# ArduinoRelayTimerSche.net
KiCad netlist of a schematic drawn in Altium Designer
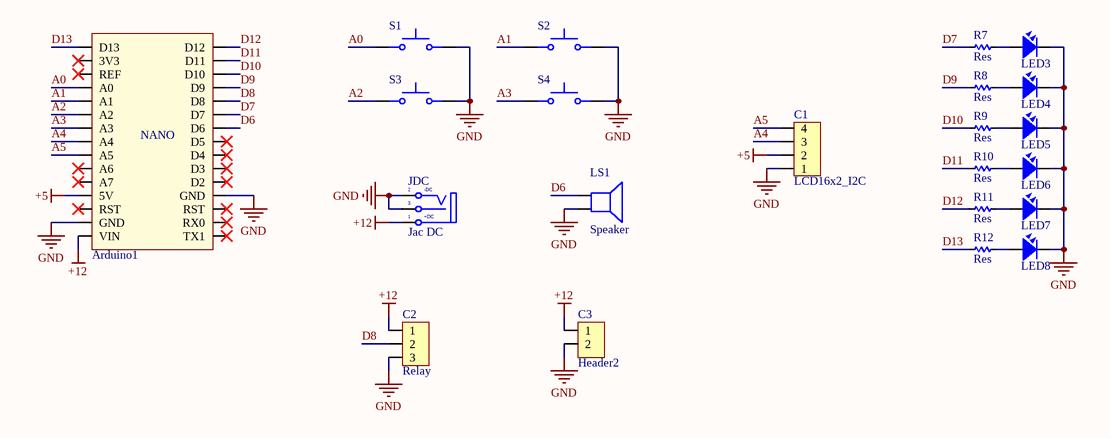
[diagram p0: ArduinoRelayTimerSche.SchDoc]

(export (version "E")
  (design (tool "Eeschema 10.0.6"))
  (components
    (comp (ref "Arduino1")
      (value "Arduino Nano")
      (footprint "Arduino Nano")
      (description "Arduino NANO")
      (libsource (lib "LIBRARY") (part "Arduino Nano"))
    )
    (comp (ref "C1")
      (value "LCD16x2_I2C")
      (footprint "Header4")
      (description "Header IDC, 4 x 1 Pin Vertical 2.54mm Pitch (Non-Boxed, Male)")
      (fields
        (field (name "MANUFACTURER") "Würth Elektronik eiSos GmbH")
        (field (name "PARTNO") "613002143121")
        (field (name "CREATED BY") "Karrer Zheng")
      )
      (libsource (lib "LIBRARY") (part "Header4"))
    )
    (comp (ref "C2")
      (value "Relay")
      (footprint "Header3")
      (description "Header IDC, 3 x 1 Pin Vertical 2.54mm Pitch (Non-Boxed, Male)")
      (fields
        (field (name "MANUFACTURER") "Würth Elektronik eiSos GmbH")
        (field (name "PARTNO") "613002143121")
        (field (name "CREATED BY") "Karrer Zheng")
      )
      (libsource (lib "LIBRARY") (part "Header3"))
    )
    (comp (ref "C3")
      (value "Header2")
      (footprint "Header2")
      (description "Header IDC, 2 x 1 Pin Vertical 2.54mm Pitch (Non-Boxed, Male)")
      (fields
        (field (name "MANUFACTURER") "Würth Elektronik eiSos GmbH")
        (field (name "PARTNO") "613002143121")
        (field (name "CREATED BY") "Karrer Zheng")
      )
      (libsource (lib "LIBRARY") (part "Header2"))
    )
    (comp (ref "JDC")
      (value "Jac DC")
      (footprint "DC0")
      (description "Jac DC input")
      (libsource (lib "LIBRARY") (part "DCIN"))
    )
    (comp (ref "LED3")
      (value "LED")
      (footprint "LED-5-Yellow")
      (description "LED Single colour Green and Red")
      (libsource (lib "LIBRARY") (part "LED"))
    )
    (comp (ref "LED4")
      (value "LED")
      (footprint "LED-5-Yellow")
      (description "LED Single colour Green and Red")
      (libsource (lib "LIBRARY") (part "LED"))
    )
    (comp (ref "LED5")
      (value "LED")
      (footprint "LED-5-Yellow")
      (description "LED Single colour Green and Red")
      (libsource (lib "LIBRARY") (part "LED"))
    )
    (comp (ref "LED6")
      (value "LED")
      (footprint "LED-5-Yellow")
      (description "LED Single colour Green and Red")
      (libsource (lib "LIBRARY") (part "LED"))
    )
    (comp (ref "LED7")
      (value "LED")
      (footprint "LED-5-Yellow")
      (description "LED Single colour Green and Red")
      (libsource (lib "LIBRARY") (part "LED"))
    )
    (comp (ref "LED8")
      (value "LED")
      (footprint "LED-5-Yellow")
      (description "LED Single colour Green and Red")
      (libsource (lib "LIBRARY") (part "LED"))
    )
    (comp (ref "LS1")
      (value "Speaker")
      (footprint "SPEAKER")
      (description "Loudspeaker")
      (fields (field (name "PUBLISHER") "Altium Limited"))
      (libsource (lib "LIBRARY") (part "Speaker"))
    )
    (comp (ref "R7")
      (value "Res")
      (footprint "RES-1/4W-SMALL")
      (fields
        (field (name "MANUFACTURER") "Generic Components")
        (field (name "PUBLISHER") "Altium Hobart Technology Centre")
      )
      (libsource (lib "LIBRARY") (part "Res"))
    )
    (comp (ref "R8")
      (value "Res")
      (footprint "RES-1/4W-SMALL")
      (fields
        (field (name "MANUFACTURER") "Generic Components")
        (field (name "PUBLISHER") "Altium Hobart Technology Centre")
      )
      (libsource (lib "LIBRARY") (part "Res"))
    )
    (comp (ref "R9")
      (value "Res")
      (footprint "RES-1/4W-SMALL")
      (fields
        (field (name "MANUFACTURER") "Generic Components")
        (field (name "PUBLISHER") "Altium Hobart Technology Centre")
      )
      (libsource (lib "LIBRARY") (part "Res"))
    )
    (comp (ref "R10")
      (value "Res")
      (footprint "RES-1/4W-SMALL")
      (fields
        (field (name "MANUFACTURER") "Generic Components")
        (field (name "PUBLISHER") "Altium Hobart Technology Centre")
      )
      (libsource (lib "LIBRARY") (part "Res"))
    )
    (comp (ref "R11")
      (value "Res")
      (footprint "RES-1/4W-SMALL")
      (fields
        (field (name "MANUFACTURER") "Generic Components")
        (field (name "PUBLISHER") "Altium Hobart Technology Centre")
      )
      (libsource (lib "LIBRARY") (part "Res"))
    )
    (comp (ref "R12")
      (value "Res")
      (footprint "RES-1/4W-SMALL")
      (fields
        (field (name "MANUFACTURER") "Generic Components")
        (field (name "PUBLISHER") "Altium Hobart Technology Centre")
      )
      (libsource (lib "LIBRARY") (part "Res"))
    )
    (comp (ref "S1")
      (value "~")
      (footprint "SW_TL59NF160Q")
      (description "SWITCH TACTILE SPST-NO 0.05A 12V")
      (fields (field (name "MF") "E-Switch") (field (name "MP") "TL59NF160Q"))
      (libsource (lib "BigTactileSwitch2pins") (part "TL59NF160Q"))
    )
    (comp (ref "S2")
      (value "~")
      (footprint "SW_TL59NF160Q")
      (description "SWITCH TACTILE SPST-NO 0.05A 12V")
      (fields (field (name "MF") "E-Switch") (field (name "MP") "TL59NF160Q"))
      (libsource (lib "BigTactileSwitch2pins") (part "TL59NF160Q"))
    )
    (comp (ref "S3")
      (value "~")
      (footprint "SW_TL59NF160Q")
      (description "SWITCH TACTILE SPST-NO 0.05A 12V")
      (fields (field (name "MF") "E-Switch") (field (name "MP") "TL59NF160Q"))
      (libsource (lib "BigTactileSwitch2pins") (part "TL59NF160Q"))
    )
    (comp (ref "S4")
      (value "~")
      (footprint "SW_TL59NF160Q")
      (description "SWITCH TACTILE SPST-NO 0.05A 12V")
      (fields (field (name "MF") "E-Switch") (field (name "MP") "TL59NF160Q"))
      (libsource (lib "BigTactileSwitch2pins") (part "TL59NF160Q"))
    )
  )
  (nets
    (net (code "1") (name "+5") (class "Default")
      (node (ref "Arduino1") (pin "5V") (pinfunction "5V_5V") (pintype "passive"))
      (node (ref "C1") (pin "2") (pinfunction "2_2") (pintype "passive"))
    )
    (net (code "2") (name "+12") (class "Default")
      (node (ref "Arduino1") (pin "VIN") (pinfunction "VIN_VIN") (pintype "passive"))
      (node (ref "C2") (pin "1") (pinfunction "1_1") (pintype "passive"))
      (node (ref "C3") (pin "1") (pinfunction "1_1") (pintype "passive"))
      (node (ref "JDC") (pin "1") (pinfunction "T_1") (pintype "passive"))
    )
    (net (code "3") (name "/A0") (class "Default")
      (node (ref "Arduino1") (pin "A0") (pinfunction "A0_A0") (pintype "passive"))
      (node (ref "S1") (pin "1") (pinfunction "1_1") (pintype "passive"))
    )
    (net (code "4") (name "/A1") (class "Default")
      (node (ref "Arduino1") (pin "A1") (pinfunction "A1_A1") (pintype "passive"))
      (node (ref "S2") (pin "1") (pinfunction "1_1") (pintype "passive"))
    )
    (net (code "5") (name "/A2") (class "Default")
      (node (ref "Arduino1") (pin "A2") (pinfunction "A2_A2") (pintype "passive"))
      (node (ref "S3") (pin "1") (pinfunction "1_1") (pintype "passive"))
    )
    (net (code "6") (name "/A3") (class "Default")
      (node (ref "Arduino1") (pin "A3") (pinfunction "A3_A3") (pintype "passive"))
      (node (ref "S4") (pin "1") (pinfunction "1_1") (pintype "passive"))
    )
    (net (code "7") (name "/A4") (class "Default")
      (node (ref "Arduino1") (pin "A4") (pinfunction "A4_A4") (pintype "passive"))
      (node (ref "C1") (pin "3") (pinfunction "3_3") (pintype "passive"))
    )
    (net (code "8") (name "/A5") (class "Default")
      (node (ref "Arduino1") (pin "A5") (pinfunction "A5_A5") (pintype "passive"))
      (node (ref "C1") (pin "4") (pinfunction "4_4") (pintype "passive"))
    )
    (net (code "9") (name "/D6") (class "Default")
      (node (ref "Arduino1") (pin "D6") (pinfunction "D6_D6") (pintype "passive"))
      (node (ref "LS1") (pin "1") (pinfunction "1_1") (pintype "passive"))
    )
    (net (code "10") (name "/D7") (class "Default")
      (node (ref "Arduino1") (pin "D7") (pinfunction "D7_D7") (pintype "passive"))
      (node (ref "R7") (pin "1") (pinfunction "1_1") (pintype "passive"))
    )
    (net (code "11") (name "/D8") (class "Default")
      (node (ref "Arduino1") (pin "D8") (pinfunction "D8_D8") (pintype "passive"))
      (node (ref "C2") (pin "2") (pinfunction "2_2") (pintype "passive"))
    )
    (net (code "12") (name "/D9") (class "Default")
      (node (ref "Arduino1") (pin "D9") (pinfunction "D9_D9") (pintype "passive"))
      (node (ref "R8") (pin "1") (pinfunction "1_1") (pintype "passive"))
    )
    (net (code "13") (name "/D10") (class "Default")
      (node (ref "Arduino1") (pin "D10") (pinfunction "D10_D10") (pintype "passive"))
      (node (ref "R9") (pin "1") (pinfunction "1_1") (pintype "passive"))
    )
    (net (code "14") (name "/D11") (class "Default")
      (node (ref "Arduino1") (pin "D11") (pinfunction "D11_D11") (pintype "passive"))
      (node (ref "R10") (pin "1") (pinfunction "1_1") (pintype "passive"))
    )
    (net (code "15") (name "/D12") (class "Default")
      (node (ref "Arduino1") (pin "D12") (pinfunction "D12_D12") (pintype "passive"))
      (node (ref "R11") (pin "1") (pinfunction "1_1") (pintype "passive"))
    )
    (net (code "16") (name "/D13") (class "Default")
      (node (ref "Arduino1") (pin "D13") (pinfunction "D13_D13") (pintype "passive"))
      (node (ref "R12") (pin "1") (pinfunction "1_1") (pintype "passive"))
    )
    (net (code "17") (name "GND") (class "Default")
      (node (ref "Arduino1") (pin "GND") (pinfunction "GND_GND") (pintype "passive"))
      (node (ref "C1") (pin "1") (pinfunction "1_1") (pintype "passive"))
      (node (ref "C2") (pin "3") (pinfunction "3_3") (pintype "passive"))
      (node (ref "C3") (pin "2") (pinfunction "2_2") (pintype "passive"))
      (node (ref "JDC") (pin "2") (pinfunction "TN_2") (pintype "passive"))
      (node (ref "JDC") (pin "3") (pinfunction "S_3") (pintype "power_in"))
      (node (ref "LED3") (pin "2") (pinfunction "2_2") (pintype "passive"))
      (node (ref "LED4") (pin "2") (pinfunction "2_2") (pintype "passive"))
      (node (ref "LED5") (pin "2") (pinfunction "2_2") (pintype "passive"))
      (node (ref "LED6") (pin "2") (pinfunction "2_2") (pintype "passive"))
      (node (ref "LED7") (pin "2") (pinfunction "2_2") (pintype "passive"))
      (node (ref "LED8") (pin "2") (pinfunction "2_2") (pintype "passive"))
      (node (ref "LS1") (pin "2") (pinfunction "2_2") (pintype "passive"))
      (node (ref "S1") (pin "2") (pinfunction "2_2") (pintype "passive"))
      (node (ref "S2") (pin "2") (pinfunction "2_2") (pintype "passive"))
      (node (ref "S3") (pin "2") (pinfunction "2_2") (pintype "passive"))
      (node (ref "S4") (pin "2") (pinfunction "2_2") (pintype "passive"))
    )
    (net (code "18") (name "Net-(LED3-Pad1)") (class "Default")
      (node (ref "LED3") (pin "1") (pinfunction "1_1") (pintype "passive"))
      (node (ref "R7") (pin "2") (pinfunction "2_2") (pintype "passive"))
    )
    (net (code "19") (name "Net-(LED4-Pad1)") (class "Default")
      (node (ref "LED4") (pin "1") (pinfunction "1_1") (pintype "passive"))
      (node (ref "R8") (pin "2") (pinfunction "2_2") (pintype "passive"))
    )
    (net (code "20") (name "Net-(LED5-Pad1)") (class "Default")
      (node (ref "LED5") (pin "1") (pinfunction "1_1") (pintype "passive"))
      (node (ref "R9") (pin "2") (pinfunction "2_2") (pintype "passive"))
    )
    (net (code "21") (name "Net-(LED6-Pad1)") (class "Default")
      (node (ref "LED6") (pin "1") (pinfunction "1_1") (pintype "passive"))
      (node (ref "R10") (pin "2") (pinfunction "2_2") (pintype "passive"))
    )
    (net (code "22") (name "Net-(LED7-Pad1)") (class "Default")
      (node (ref "LED7") (pin "1") (pinfunction "1_1") (pintype "passive"))
      (node (ref "R11") (pin "2") (pinfunction "2_2") (pintype "passive"))
    )
    (net (code "23") (name "Net-(LED8-Pad1)") (class "Default")
      (node (ref "LED8") (pin "1") (pinfunction "1_1") (pintype "passive"))
      (node (ref "R12") (pin "2") (pinfunction "2_2") (pintype "passive"))
    )
    (net (code "24") (name "unconnected-(Arduino1-Pad3V3)") (class "Default")
      (node (ref "Arduino1") (pin "3V3") (pinfunction "3V3_3V3") (pintype "passive+no_connect"))
    )
    (net (code "25") (name "unconnected-(Arduino1-PadA6)") (class "Default")
      (node (ref "Arduino1") (pin "A6") (pinfunction "A6_A6") (pintype "passive+no_connect"))
    )
    (net (code "26") (name "unconnected-(Arduino1-PadA7)") (class "Default")
      (node (ref "Arduino1") (pin "A7") (pinfunction "A7_A7") (pintype "passive+no_connect"))
    )
    (net (code "27") (name "unconnected-(Arduino1-PadD2)") (class "Default")
      (node (ref "Arduino1") (pin "D2") (pinfunction "D2_D2") (pintype "passive+no_connect"))
    )
    (net (code "28") (name "unconnected-(Arduino1-PadD3)") (class "Default")
      (node (ref "Arduino1") (pin "D3") (pinfunction "D3_D3") (pintype "passive+no_connect"))
    )
    (net (code "29") (name "unconnected-(Arduino1-PadD4)") (class "Default")
      (node (ref "Arduino1") (pin "D4") (pinfunction "D4_D4") (pintype "passive+no_connect"))
    )
    (net (code "30") (name "unconnected-(Arduino1-PadD5)") (class "Default")
      (node (ref "Arduino1") (pin "D5") (pinfunction "D5_D5") (pintype "passive+no_connect"))
    )
    (net (code "31") (name "unconnected-(Arduino1-PadREF)") (class "Default")
      (node (ref "Arduino1") (pin "REF") (pinfunction "REF_REF") (pintype "passive+no_connect"))
    )
    (net (code "32") (name "unconnected-(Arduino1-PadRST)") (class "Default")
      (node (ref "Arduino1") (pin "RST") (pinfunction "RST_RST") (pintype "passive+no_connect"))
    )
    (net (code "33") (name "unconnected-(Arduino1-PadRST)_1") (class "Default")
      (node (ref "Arduino1") (pin "RST") (pinfunction "RST_RST") (pintype "passive+no_connect"))
    )
    (net (code "34") (name "unconnected-(Arduino1-PadRX0)") (class "Default")
      (node (ref "Arduino1") (pin "RX0") (pinfunction "RX0_RX0") (pintype "passive+no_connect"))
    )
    (net (code "35") (name "unconnected-(Arduino1-PadTX1)") (class "Default")
      (node (ref "Arduino1") (pin "TX1") (pinfunction "TX1_TX1") (pintype "passive+no_connect"))
    )
  )
)
